# LEDs_FMU3_REV_C.net
KiCad netlist of a schematic drawn in Altium Designer
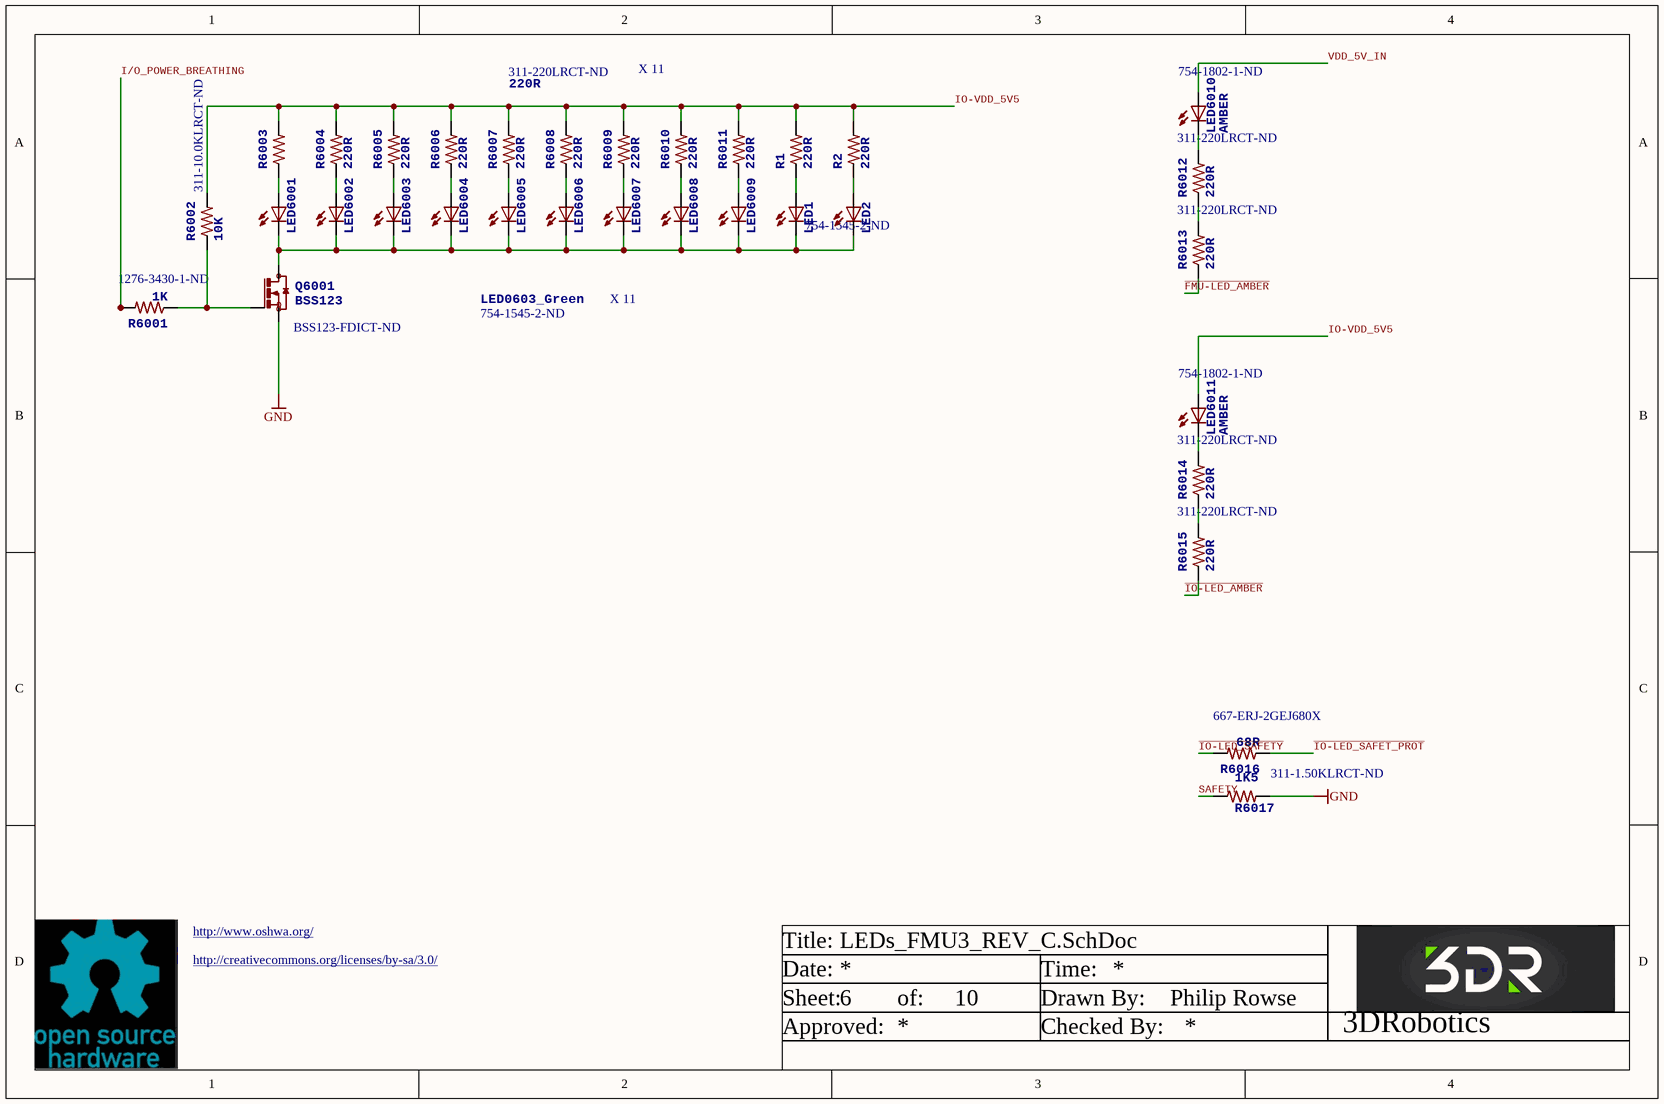
[diagram p0: LEDs_FMU3_REV_C.SchDoc]

(export (version "E")
  (design (tool "Eeschema 10.0.6"))
  (components
    (comp (ref "LED1")
      (value "LED0603_Green")
      (footprint "0603-LED-Blue")
      (description "LED GREEN ROUND CLEAR SMD")
      (fields
        (field (name "SUPPLIER PART NUMBER 1") "754-1545-2-ND")
        (field (name "3DR_PARTNO") "ECM0494")
        (field (name "PARTNO") "APTD1608CGCK")
      )
      (libsource (lib "pixhawk2") (part "LED0603_Blue"))
    )
    (comp (ref "LED2")
      (value "LED0603_Green")
      (footprint "0603-LED-Blue")
      (description "LED GREEN ROUND CLEAR SMD")
      (fields (field (name "3DR_PARTNO") "ECM0494") (field (name "PARTNO") "APTD1608CGCK"))
      (libsource (lib "pixhawk2") (part "LED0603_Blue"))
    )
    (comp (ref "LED6001")
      (value "LED0603_Green")
      (footprint "0603-LED-Blue")
      (description "LED GREEN ROUND CLEAR SMD")
      (fields
        (field (name "SUPPLIER PART NUMBER 1") "754-1545-2-ND")
        (field (name "3DR_PARTNO") "ECM0494")
        (field (name "PARTNO") "APTD1608CGCK")
      )
      (libsource (lib "pixhawk2") (part "LED0603_Blue"))
    )
    (comp (ref "LED6002")
      (value "LED0603_Green")
      (footprint "0603-LED-Blue")
      (description "LED GREEN ROUND CLEAR SMD")
      (fields (field (name "3DR_PARTNO") "ECM0494") (field (name "PARTNO") "APTD1608CGCK"))
      (libsource (lib "pixhawk2") (part "LED0603_Blue"))
    )
    (comp (ref "LED6003")
      (value "LED0603_Green")
      (footprint "0603-LED-Blue")
      (description "LED GREEN ROUND CLEAR SMD")
      (fields (field (name "3DR_PARTNO") "ECM0494") (field (name "PARTNO") "APTD1608CGCK"))
      (libsource (lib "pixhawk2") (part "LED0603_Blue"))
    )
    (comp (ref "LED6004")
      (value "LED0603_Green")
      (footprint "0603-LED-Blue")
      (description "LED GREEN ROUND CLEAR SMD")
      (fields (field (name "3DR_PARTNO") "ECM0494") (field (name "PARTNO") "APTD1608CGCK"))
      (libsource (lib "pixhawk2") (part "LED0603_Blue"))
    )
    (comp (ref "LED6005")
      (value "LED0603_Green")
      (footprint "0603-LED-Blue")
      (description "LED GREEN ROUND CLEAR SMD")
      (fields (field (name "3DR_PARTNO") "ECM0494") (field (name "PARTNO") "APTD1608CGCK"))
      (libsource (lib "pixhawk2") (part "LED0603_Blue"))
    )
    (comp (ref "LED6006")
      (value "LED0603_Green")
      (footprint "0603-LED-Blue")
      (description "LED GREEN ROUND CLEAR SMD")
      (fields (field (name "3DR_PARTNO") "ECM0494") (field (name "PARTNO") "APTD1608CGCK"))
      (libsource (lib "pixhawk2") (part "LED0603_Blue"))
    )
    (comp (ref "LED6007")
      (value "LED0603_Green")
      (footprint "0603-LED-Blue")
      (description "LED GREEN ROUND CLEAR SMD")
      (fields (field (name "3DR_PARTNO") "ECM0494") (field (name "PARTNO") "APTD1608CGCK"))
      (libsource (lib "pixhawk2") (part "LED0603_Blue"))
    )
    (comp (ref "LED6008")
      (value "LED0603_Green")
      (footprint "0603-LED-Blue")
      (description "LED GREEN ROUND CLEAR SMD")
      (fields (field (name "3DR_PARTNO") "ECM0494") (field (name "PARTNO") "APTD1608CGCK"))
      (libsource (lib "pixhawk2") (part "LED0603_Blue"))
    )
    (comp (ref "LED6009")
      (value "LED0603_Green")
      (footprint "0603-LED-Blue")
      (description "LED GREEN ROUND CLEAR SMD")
      (fields (field (name "3DR_PARTNO") "ECM0494") (field (name "PARTNO") "APTD1608CGCK"))
      (libsource (lib "pixhawk2") (part "LED0603_Blue"))
    )
    (comp (ref "LED6010")
      (value "AMBER")
      (footprint "0603-LED")
      (description "LED 1.6X0.8 DOME ORN CLEAR SMD")
      (fields
        (field (name "PARTNO") "APTD1608SECK")
        (field (name "SUPPLIER PART NUMBER 1") "754-1802-1-ND")
        (field (name "3DR_PARTNO") "ECM0515")
      )
      (libsource (lib "pixhawk2") (part "LED0603"))
    )
    (comp (ref "LED6011")
      (value "AMBER")
      (footprint "0603-LED")
      (description "LED 1.6X0.8 DOME ORN CLEAR SMD")
      (fields
        (field (name "PARTNO") "APTD1608SECK")
        (field (name "SUPPLIER PART NUMBER 1") "754-1802-1-ND")
        (field (name "3DR_PARTNO") "ECM0515")
      )
      (libsource (lib "pixhawk2") (part "LED0603"))
    )
    (comp (ref "Q6001")
      (value "BSS123")
      (footprint "SOT23")
      (description "MOSFET N-CH 100V 170MA SOT23-3")
      (fields (field (name "SUPPLIER PART NUMBER 1") "BSS123-FDICT-ND") (field (name "3DR_PARTNO") "ECM0547"))
      (libsource (lib "transistor-small-signal") (part "BSS123"))
    )
    (comp (ref "R1")
      (value "220R")
      (footprint "0402-RES")
      (description "RES 220 OHM 1/16W 1% 0402 SMD")
      (fields (field (name "PARTNO") "RC0402FR-07220RL") (field (name "3DR_PARTNO") "ECM0821"))
      (libsource (lib "pixhawk2") (part "RESISTOR0402-RES"))
    )
    (comp (ref "R2")
      (value "220R")
      (footprint "0402-RES")
      (description "RES 220 OHM 1/16W 1% 0402 SMD")
      (fields (field (name "PARTNO") "RC0402FR-07220RL") (field (name "3DR_PARTNO") "ECM0821"))
      (libsource (lib "pixhawk2") (part "RESISTOR0402-RES"))
    )
    (comp (ref "R6001")
      (value "1K")
      (footprint "0402-RES")
      (description "RES 1K OHM 1/16W 1% 0402")
      (fields
        (field (name "PARTNO") "RC1005F102CS")
        (field (name "SUPPLIER PART NUMBER 1") "1276-3430-1-ND")
        (field (name "3DR_PARTNO") "ECM0804")
      )
      (libsource (lib "pixhawk2") (part "RESISTOR0402-RES"))
    )
    (comp (ref "R6002")
      (value "10K")
      (footprint "0402-RES")
      (description "RES 10K OHM 1/16W 1% 0402 SMD")
      (fields
        (field (name "PARTNO") "RC0402FR-0710KL")
        (field (name "SUPPLIER PART NUMBER 1") "311-10.0KLRCT-ND")
        (field (name "3DR_PARTNO") "ECM0800")
      )
      (libsource (lib "pixhawk2") (part "RESISTOR0402-RES"))
    )
    (comp (ref "R6003")
      (value "220R")
      (footprint "0402-RES")
      (description "RES 220 OHM 1/16W 1% 0402 SMD")
      (fields
        (field (name "PARTNO") "RC0402FR-07220RL")
        (field (name "SUPPLIER PART NUMBER 1") "311-220LRCT-ND")
        (field (name "3DR_PARTNO") "ECM0821")
      )
      (libsource (lib "pixhawk2") (part "RESISTOR0402-RES"))
    )
    (comp (ref "R6004")
      (value "220R")
      (footprint "0402-RES")
      (description "RES 220 OHM 1/16W 1% 0402 SMD")
      (fields (field (name "PARTNO") "RC0402FR-07220RL") (field (name "3DR_PARTNO") "ECM0821"))
      (libsource (lib "pixhawk2") (part "RESISTOR0402-RES"))
    )
    (comp (ref "R6005")
      (value "220R")
      (footprint "0402-RES")
      (description "RES 220 OHM 1/16W 1% 0402 SMD")
      (fields (field (name "PARTNO") "RC0402FR-07220RL") (field (name "3DR_PARTNO") "ECM0821"))
      (libsource (lib "pixhawk2") (part "RESISTOR0402-RES"))
    )
    (comp (ref "R6006")
      (value "220R")
      (footprint "0402-RES")
      (description "RES 220 OHM 1/16W 1% 0402 SMD")
      (fields (field (name "PARTNO") "RC0402FR-07220RL") (field (name "3DR_PARTNO") "ECM0821"))
      (libsource (lib "pixhawk2") (part "RESISTOR0402-RES"))
    )
    (comp (ref "R6007")
      (value "220R")
      (footprint "0402-RES")
      (description "RES 220 OHM 1/16W 1% 0402 SMD")
      (fields (field (name "PARTNO") "RC0402FR-07220RL") (field (name "3DR_PARTNO") "ECM0821"))
      (libsource (lib "pixhawk2") (part "RESISTOR0402-RES"))
    )
    (comp (ref "R6008")
      (value "220R")
      (footprint "0402-RES")
      (description "RES 220 OHM 1/16W 1% 0402 SMD")
      (fields (field (name "PARTNO") "RC0402FR-07220RL") (field (name "3DR_PARTNO") "ECM0821"))
      (libsource (lib "pixhawk2") (part "RESISTOR0402-RES"))
    )
    (comp (ref "R6009")
      (value "220R")
      (footprint "0402-RES")
      (description "RES 220 OHM 1/16W 1% 0402 SMD")
      (fields (field (name "PARTNO") "RC0402FR-07220RL") (field (name "3DR_PARTNO") "ECM0821"))
      (libsource (lib "pixhawk2") (part "RESISTOR0402-RES"))
    )
    (comp (ref "R6010")
      (value "220R")
      (footprint "0402-RES")
      (description "RES 220 OHM 1/16W 1% 0402 SMD")
      (fields (field (name "PARTNO") "RC0402FR-07220RL") (field (name "3DR_PARTNO") "ECM0821"))
      (libsource (lib "pixhawk2") (part "RESISTOR0402-RES"))
    )
    (comp (ref "R6011")
      (value "220R")
      (footprint "0402-RES")
      (description "RES 220 OHM 1/16W 1% 0402 SMD")
      (fields (field (name "PARTNO") "RC0402FR-07220RL") (field (name "3DR_PARTNO") "ECM0821"))
      (libsource (lib "pixhawk2") (part "RESISTOR0402-RES"))
    )
    (comp (ref "R6012")
      (value "220R")
      (footprint "0402-RES")
      (description "RES 220 OHM 1/16W 1% 0402 SMD")
      (fields
        (field (name "PARTNO") "RC0402FR-07220RL")
        (field (name "SUPPLIER PART NUMBER 1") "311-220LRCT-ND")
        (field (name "3DR_PARTNO") "ECM0821")
      )
      (libsource (lib "pixhawk2") (part "RESISTOR0402-RES"))
    )
    (comp (ref "R6013")
      (value "220R")
      (footprint "0402-RES")
      (description "RES 220 OHM 1/16W 1% 0402 SMD")
      (fields
        (field (name "PARTNO") "RC0402FR-07220RL")
        (field (name "SUPPLIER PART NUMBER 1") "311-220LRCT-ND")
        (field (name "3DR_PARTNO") "ECM0821")
      )
      (libsource (lib "pixhawk2") (part "RESISTOR0402-RES"))
    )
    (comp (ref "R6014")
      (value "220R")
      (footprint "0402-RES")
      (description "RES 220 OHM 1/16W 1% 0402 SMD")
      (fields
        (field (name "PARTNO") "RC0402FR-07220RL")
        (field (name "SUPPLIER PART NUMBER 1") "311-220LRCT-ND")
        (field (name "3DR_PARTNO") "ECM0821")
      )
      (libsource (lib "pixhawk2") (part "RESISTOR0402-RES"))
    )
    (comp (ref "R6015")
      (value "220R")
      (footprint "0402-RES")
      (description "RES 220 OHM 1/16W 1% 0402 SMD")
      (fields
        (field (name "PARTNO") "RC0402FR-07220RL")
        (field (name "SUPPLIER PART NUMBER 1") "311-220LRCT-ND")
        (field (name "3DR_PARTNO") "ECM0821")
      )
      (libsource (lib "pixhawk2") (part "RESISTOR0402-RES"))
    )
    (comp (ref "R6016")
      (value "68R")
      (footprint "0402-RES")
      (description "Thick Film Resistors - SMD 0402 68ohms 5% Tol")
      (fields
        (field (name "PARTNO") "ERJ-2GEJ680X")
        (field (name "SUPPLIER PART NUMBER 1") "667-ERJ-2GEJ680X")
        (field (name "3DR_PARTNO") "ECM0816")
      )
      (libsource (lib "pixhawk2") (part "RESISTOR0402-RES"))
    )
    (comp (ref "R6017")
      (value "1K5")
      (footprint "0402-RES")
      (description "RES 1.5K OHM 1/16W 1% 0402 SMD")
      (fields
        (field (name "SUPPLIER PART NUMBER 1") "311-1.50KLRCT-ND")
        (field (name "3DR_PARTNO") "ECM0803")
        (field (name "PARTNO") "RC0402FR-071K5L")
      )
      (libsource (lib "pixhawk2") (part "RESISTOR0402-RES"))
    )
  )
  (nets
    (net (code "1") (name "/IO-VDD_5V5") (class "Default")
      (node (ref "LED6011") (pin "A") (pinfunction "A_A") (pintype "passive"))
      (node (ref "R1") (pin "P$2") (pinfunction "2_P$2") (pintype "passive"))
      (node (ref "R2") (pin "P$2") (pinfunction "2_P$2") (pintype "passive"))
      (node (ref "R6002") (pin "P$2") (pinfunction "2_P$2") (pintype "passive"))
      (node (ref "R6003") (pin "P$2") (pinfunction "2_P$2") (pintype "passive"))
      (node (ref "R6004") (pin "P$2") (pinfunction "2_P$2") (pintype "passive"))
      (node (ref "R6005") (pin "P$2") (pinfunction "2_P$2") (pintype "passive"))
      (node (ref "R6006") (pin "P$2") (pinfunction "2_P$2") (pintype "passive"))
      (node (ref "R6007") (pin "P$2") (pinfunction "2_P$2") (pintype "passive"))
      (node (ref "R6008") (pin "P$2") (pinfunction "2_P$2") (pintype "passive"))
      (node (ref "R6009") (pin "P$2") (pinfunction "2_P$2") (pintype "passive"))
      (node (ref "R6010") (pin "P$2") (pinfunction "2_P$2") (pintype "passive"))
      (node (ref "R6011") (pin "P$2") (pinfunction "2_P$2") (pintype "passive"))
    )
    (net (code "2") (name "/I{slash}O_POWER_BREATHING") (class "Default")
      (node (ref "R6001") (pin "P$2") (pinfunction "2_P$2") (pintype "passive"))
    )
    (net (code "3") (name "/SAFETY") (class "Default")
      (node (ref "R6017") (pin "P$1") (pinfunction "1_P$1") (pintype "passive"))
    )
    (net (code "4") (name "/VDD_5V_IN") (class "Default")
      (node (ref "LED6010") (pin "A") (pinfunction "A_A") (pintype "passive"))
    )
    (net (code "5") (name "/~{FMU-LED_AMBER}") (class "Default")
      (node (ref "R6013") (pin "P$1") (pinfunction "1_P$1") (pintype "passive"))
    )
    (net (code "6") (name "/~{IO-LED_AMBER}") (class "Default")
      (node (ref "R6015") (pin "P$1") (pinfunction "1_P$1") (pintype "passive"))
    )
    (net (code "7") (name "/~{IO-LED_SAFETY}") (class "Default")
      (node (ref "R6016") (pin "P$2") (pinfunction "2_P$2") (pintype "passive"))
    )
    (net (code "8") (name "/~{IO-LED_SAFET_PROT}") (class "Default")
      (node (ref "R6016") (pin "P$1") (pinfunction "1_P$1") (pintype "passive"))
    )
    (net (code "9") (name "GND") (class "Default")
      (node (ref "Q6001") (pin "2") (pinfunction "S_2") (pintype "passive"))
      (node (ref "R6017") (pin "P$2") (pinfunction "2_P$2") (pintype "passive"))
    )
    (net (code "10") (name "Net-(Q6001-D)") (class "Default")
      (node (ref "LED1") (pin "C") (pinfunction "C_C") (pintype "passive"))
      (node (ref "LED2") (pin "C") (pinfunction "C_C") (pintype "passive"))
      (node (ref "LED6001") (pin "C") (pinfunction "C_C") (pintype "passive"))
      (node (ref "LED6002") (pin "C") (pinfunction "C_C") (pintype "passive"))
      (node (ref "LED6003") (pin "C") (pinfunction "C_C") (pintype "passive"))
      (node (ref "LED6004") (pin "C") (pinfunction "C_C") (pintype "passive"))
      (node (ref "LED6005") (pin "C") (pinfunction "C_C") (pintype "passive"))
      (node (ref "LED6006") (pin "C") (pinfunction "C_C") (pintype "passive"))
      (node (ref "LED6007") (pin "C") (pinfunction "C_C") (pintype "passive"))
      (node (ref "LED6008") (pin "C") (pinfunction "C_C") (pintype "passive"))
      (node (ref "LED6009") (pin "C") (pinfunction "C_C") (pintype "passive"))
      (node (ref "Q6001") (pin "3") (pinfunction "D_3") (pintype "passive"))
    )
    (net (code "11") (name "Net-(Q6001-G)") (class "Default")
      (node (ref "Q6001") (pin "1") (pinfunction "G_1") (pintype "passive"))
      (node (ref "R6001") (pin "P$1") (pinfunction "1_P$1") (pintype "passive"))
      (node (ref "R6002") (pin "P$1") (pinfunction "1_P$1") (pintype "passive"))
    )
    (net (code "12") (name "Net-(R1-1)") (class "Default")
      (node (ref "LED1") (pin "A") (pinfunction "A_A") (pintype "passive"))
      (node (ref "R1") (pin "P$1") (pinfunction "1_P$1") (pintype "passive"))
    )
    (net (code "13") (name "Net-(R2-1)") (class "Default")
      (node (ref "LED2") (pin "A") (pinfunction "A_A") (pintype "passive"))
      (node (ref "R2") (pin "P$1") (pinfunction "1_P$1") (pintype "passive"))
    )
    (net (code "14") (name "Net-(R6003-1)") (class "Default")
      (node (ref "LED6001") (pin "A") (pinfunction "A_A") (pintype "passive"))
      (node (ref "R6003") (pin "P$1") (pinfunction "1_P$1") (pintype "passive"))
    )
    (net (code "15") (name "Net-(R6004-1)") (class "Default")
      (node (ref "LED6002") (pin "A") (pinfunction "A_A") (pintype "passive"))
      (node (ref "R6004") (pin "P$1") (pinfunction "1_P$1") (pintype "passive"))
    )
    (net (code "16") (name "Net-(R6005-1)") (class "Default")
      (node (ref "LED6003") (pin "A") (pinfunction "A_A") (pintype "passive"))
      (node (ref "R6005") (pin "P$1") (pinfunction "1_P$1") (pintype "passive"))
    )
    (net (code "17") (name "Net-(R6006-1)") (class "Default")
      (node (ref "LED6004") (pin "A") (pinfunction "A_A") (pintype "passive"))
      (node (ref "R6006") (pin "P$1") (pinfunction "1_P$1") (pintype "passive"))
    )
    (net (code "18") (name "Net-(R6007-1)") (class "Default")
      (node (ref "LED6005") (pin "A") (pinfunction "A_A") (pintype "passive"))
      (node (ref "R6007") (pin "P$1") (pinfunction "1_P$1") (pintype "passive"))
    )
    (net (code "19") (name "Net-(R6008-1)") (class "Default")
      (node (ref "LED6006") (pin "A") (pinfunction "A_A") (pintype "passive"))
      (node (ref "R6008") (pin "P$1") (pinfunction "1_P$1") (pintype "passive"))
    )
    (net (code "20") (name "Net-(R6009-1)") (class "Default")
      (node (ref "LED6007") (pin "A") (pinfunction "A_A") (pintype "passive"))
      (node (ref "R6009") (pin "P$1") (pinfunction "1_P$1") (pintype "passive"))
    )
    (net (code "21") (name "Net-(R6010-1)") (class "Default")
      (node (ref "LED6008") (pin "A") (pinfunction "A_A") (pintype "passive"))
      (node (ref "R6010") (pin "P$1") (pinfunction "1_P$1") (pintype "passive"))
    )
    (net (code "22") (name "Net-(R6011-1)") (class "Default")
      (node (ref "LED6009") (pin "A") (pinfunction "A_A") (pintype "passive"))
      (node (ref "R6011") (pin "P$1") (pinfunction "1_P$1") (pintype "passive"))
    )
    (net (code "23") (name "Net-(R6012-1)") (class "Default")
      (node (ref "R6012") (pin "P$1") (pinfunction "1_P$1") (pintype "passive"))
      (node (ref "R6013") (pin "P$2") (pinfunction "2_P$2") (pintype "passive"))
    )
    (net (code "24") (name "Net-(R6012-2)") (class "Default")
      (node (ref "LED6010") (pin "C") (pinfunction "C_C") (pintype "passive"))
      (node (ref "R6012") (pin "P$2") (pinfunction "2_P$2") (pintype "passive"))
    )
    (net (code "25") (name "Net-(R6014-1)") (class "Default")
      (node (ref "R6014") (pin "P$1") (pinfunction "1_P$1") (pintype "passive"))
      (node (ref "R6015") (pin "P$2") (pinfunction "2_P$2") (pintype "passive"))
    )
    (net (code "26") (name "Net-(R6014-2)") (class "Default")
      (node (ref "LED6011") (pin "C") (pinfunction "C_C") (pintype "passive"))
      (node (ref "R6014") (pin "P$2") (pinfunction "2_P$2") (pintype "passive"))
    )
  )
)
